# Synchronous_Buck_Converter.net
KiCad netlist of a schematic drawn in Altium Designer
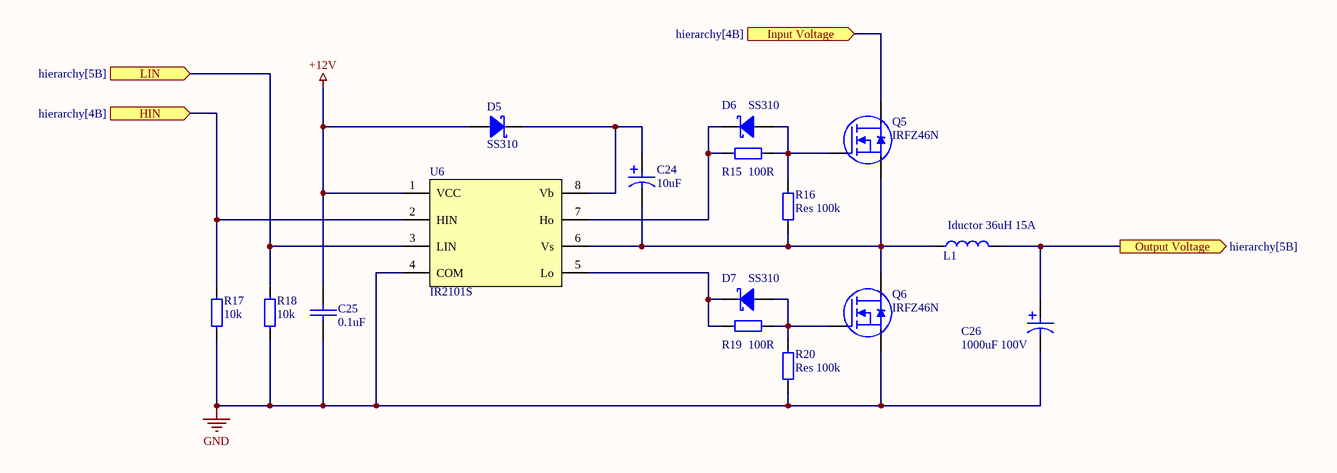
[diagram p0: Synchronous Buck Converter.SchDoc]

(export (version "E")
  (design (tool "Eeschema 10.0.6"))
  (components
    (comp (ref "C24")
      (value "10uF")
      (footprint "Bar Cap 5x5.4")
      (description "ECAP SMD,  35V")
      (fields (field (name "PART NUMBER") "ECAPSMD10uF/35V") (field (name "MANUFACTURER") "China"))
      (libsource (lib "BRT_Components") (part "Cap Pol 10uF"))
    )
    (comp (ref "C25")
      (value "0.1uF")
      (footprint "0805 Capicator")
      (description "0.1uF X7R 25V 10% 0805")
      (fields
        (field (name "MANUFACTURER") "Murata Manufacturing")
        (field (name "PART NUMBER") "GRM21BR71E104KA01L")
      )
      (libsource (lib "BRT_Components") (part "Cap 0.1uF (0805)"))
    )
    (comp (ref "C26")
      (value "1000uF 100V")
      (description "1000мкФ, 100В, 105°C, 20%, 18*40мм P:7,5мм")
      (libsource (lib "Altium_Library") (part "Capacitor 1000uF 100V"))
    )
    (comp (ref "D5")
      (value "SS310")
      (footprint "DIODE: SMB")
      (description "100B 3.0A Schottky diode")
      (libsource (lib "Altium_Library") (part "Schottky diode SS310"))
    )
    (comp (ref "D6")
      (value "SS310")
      (footprint "DIODE: SMB")
      (description "100B 3.0A Schottky diode")
      (libsource (lib "Altium_Library") (part "Schottky diode SS310"))
    )
    (comp (ref "D7")
      (value "SS310")
      (footprint "DIODE: SMB")
      (description "100B 3.0A Schottky diode")
      (libsource (lib "Altium_Library") (part "Schottky diode SS310"))
    )
    (comp (ref "L1")
      (value "Iductor 36uH 15A")
      (description "Handmade inductor 36uH")
      (libsource (lib "Altium_Library") (part "Iductor 36uH 15A"))
    )
    (comp (ref "Q5")
      (value "IRFZ46N")
      (footprint "TO220")
      (description "MOSFT 55V 46A 16.5mOhm 48nC")
      (libsource (lib "Altium_Library") (part "MOSFET-N IRFZ46N"))
    )
    (comp (ref "Q6")
      (value "IRFZ46N")
      (footprint "TO220")
      (description "MOSFT 55V 46A 16.5mOhm 48nC")
      (libsource (lib "Altium_Library") (part "MOSFET-N IRFZ46N"))
    )
    (comp (ref "R15")
      (value "100R")
      (footprint "0805 Resistor")
      (description "0.125W 0805 100R, 1%")
      (fields (field (name "PART NUMBER") "RC0805FR-07100RL") (field (name "MANUFACTURER") "Taiwan"))
      (libsource (lib "BRT_Components") (part "Res 100R (0805)"))
    )
    (comp (ref "R16")
      (value "Res 100k")
      (footprint "0805 Resistor")
      (description "0.125W 0805 100k, 1%")
      (fields (field (name "PART NUMBER") "RC0805FR-07100KL") (field (name "MANUFACTURER") "Taiwan"))
      (libsource (lib "BRT_Components") (part "Res 100k (0805)"))
    )
    (comp (ref "R17")
      (value "10k")
      (footprint "0805 Resistor")
      (description "0.125W 0805 10k, 1%")
      (fields (field (name "PART NUMBER") "RC0805FR-0710KL") (field (name "MANUFACTURER") "Taiwan"))
      (libsource (lib "BRT_Components") (part "Res 10k (0805)"))
    )
    (comp (ref "R18")
      (value "10k")
      (footprint "0805 Resistor")
      (description "0.125W 0805 10k, 1%")
      (fields (field (name "PART NUMBER") "RC0805FR-0710KL") (field (name "MANUFACTURER") "Taiwan"))
      (libsource (lib "BRT_Components") (part "Res 10k (0805)"))
    )
    (comp (ref "R19")
      (value "100R")
      (footprint "0805 Resistor")
      (description "0.125W 0805 100R, 1%")
      (fields (field (name "PART NUMBER") "RC0805FR-07100RL") (field (name "MANUFACTURER") "Taiwan"))
      (libsource (lib "BRT_Components") (part "Res 100R (0805)"))
    )
    (comp (ref "R20")
      (value "Res 100k")
      (footprint "0805 Resistor")
      (description "0.125W 0805 100k, 1%")
      (fields (field (name "PART NUMBER") "RC0805FR-07100KL") (field (name "MANUFACTURER") "Taiwan"))
      (libsource (lib "BRT_Components") (part "Res 100k (0805)"))
    )
    (comp (ref "U6")
      (value "IR2101S")
      (footprint "8-SOIC")
      (description "High and Low side driver. SOIC8 case")
      (libsource (lib "Altium_Library") (part "MOSFET Driver IR2101S"))
    )
  )
  (nets
    (net (code "1") (name "+12V") (class "Default")
      (node (ref "C25") (pin "2") (pinfunction "2_2") (pintype "passive"))
      (node (ref "D5") (pin "1") (pinfunction "1_1") (pintype "passive"))
      (node (ref "U6") (pin "1") (pinfunction "VCC_1") (pintype "passive"))
    )
    (net (code "2") (name "/HIN") (class "Default")
      (node (ref "R17") (pin "2") (pinfunction "2_2") (pintype "passive"))
      (node (ref "U6") (pin "2") (pinfunction "HIN_2") (pintype "passive"))
    )
    (net (code "3") (name "/Input Voltage") (class "Default")
      (node (ref "Q5") (pin "2") (pinfunction "Drain_2") (pintype "passive"))
    )
    (net (code "4") (name "/LIN") (class "Default")
      (node (ref "R18") (pin "2") (pinfunction "2_2") (pintype "passive"))
      (node (ref "U6") (pin "3") (pinfunction "LIN_3") (pintype "passive"))
    )
    (net (code "5") (name "/Output Voltage") (class "Default")
      (node (ref "C26") (pin "2") (pinfunction "2_2") (pintype "passive"))
      (node (ref "L1") (pin "2") (pinfunction "2_2") (pintype "passive"))
    )
    (net (code "6") (name "GND") (class "Default")
      (node (ref "C25") (pin "1") (pinfunction "1_1") (pintype "passive"))
      (node (ref "C26") (pin "1") (pinfunction "1_1") (pintype "passive"))
      (node (ref "Q6") (pin "3") (pinfunction "Source_3") (pintype "passive"))
      (node (ref "R17") (pin "1") (pinfunction "1_1") (pintype "passive"))
      (node (ref "R18") (pin "1") (pinfunction "1_1") (pintype "passive"))
      (node (ref "R20") (pin "1") (pinfunction "1_1") (pintype "passive"))
      (node (ref "U6") (pin "4") (pinfunction "COM_4") (pintype "passive"))
    )
    (net (code "7") (name "Net-(Q5-Gate)") (class "Default")
      (node (ref "D6") (pin "1") (pinfunction "1_1") (pintype "passive"))
      (node (ref "Q5") (pin "1") (pinfunction "Gate_1") (pintype "passive"))
      (node (ref "R15") (pin "2") (pinfunction "2_2") (pintype "passive"))
      (node (ref "R16") (pin "2") (pinfunction "2_2") (pintype "passive"))
    )
    (net (code "8") (name "Net-(Q5-Source)") (class "Default")
      (node (ref "C24") (pin "1") (pinfunction "1_1") (pintype "passive"))
      (node (ref "L1") (pin "1") (pinfunction "1_1") (pintype "passive"))
      (node (ref "Q5") (pin "3") (pinfunction "Source_3") (pintype "passive"))
      (node (ref "Q6") (pin "2") (pinfunction "Drain_2") (pintype "passive"))
      (node (ref "R16") (pin "1") (pinfunction "1_1") (pintype "passive"))
      (node (ref "U6") (pin "6") (pinfunction "Vs_6") (pintype "passive"))
    )
    (net (code "9") (name "Net-(Q6-Gate)") (class "Default")
      (node (ref "D7") (pin "1") (pinfunction "1_1") (pintype "passive"))
      (node (ref "Q6") (pin "1") (pinfunction "Gate_1") (pintype "passive"))
      (node (ref "R19") (pin "2") (pinfunction "2_2") (pintype "passive"))
      (node (ref "R20") (pin "2") (pinfunction "2_2") (pintype "passive"))
    )
    (net (code "10") (name "Net-(U6-Ho)") (class "Default")
      (node (ref "D6") (pin "2") (pinfunction "2_2") (pintype "passive"))
      (node (ref "R15") (pin "1") (pinfunction "1_1") (pintype "passive"))
      (node (ref "U6") (pin "7") (pinfunction "Ho_7") (pintype "passive"))
    )
    (net (code "11") (name "Net-(U6-Lo)") (class "Default")
      (node (ref "D7") (pin "2") (pinfunction "2_2") (pintype "passive"))
      (node (ref "R19") (pin "1") (pinfunction "1_1") (pintype "passive"))
      (node (ref "U6") (pin "5") (pinfunction "Lo_5") (pintype "passive"))
    )
    (net (code "12") (name "Net-(U6-Vb)") (class "Default")
      (node (ref "C24") (pin "2") (pinfunction "2_2") (pintype "passive"))
      (node (ref "D5") (pin "2") (pinfunction "2_2") (pintype "passive"))
      (node (ref "U6") (pin "8") (pinfunction "Vb_8") (pintype "passive"))
    )
  )
)
